# rapidshark-display-shifter-mk-1_1.net
KiCad netlist of a schematic drawn in EAGLE
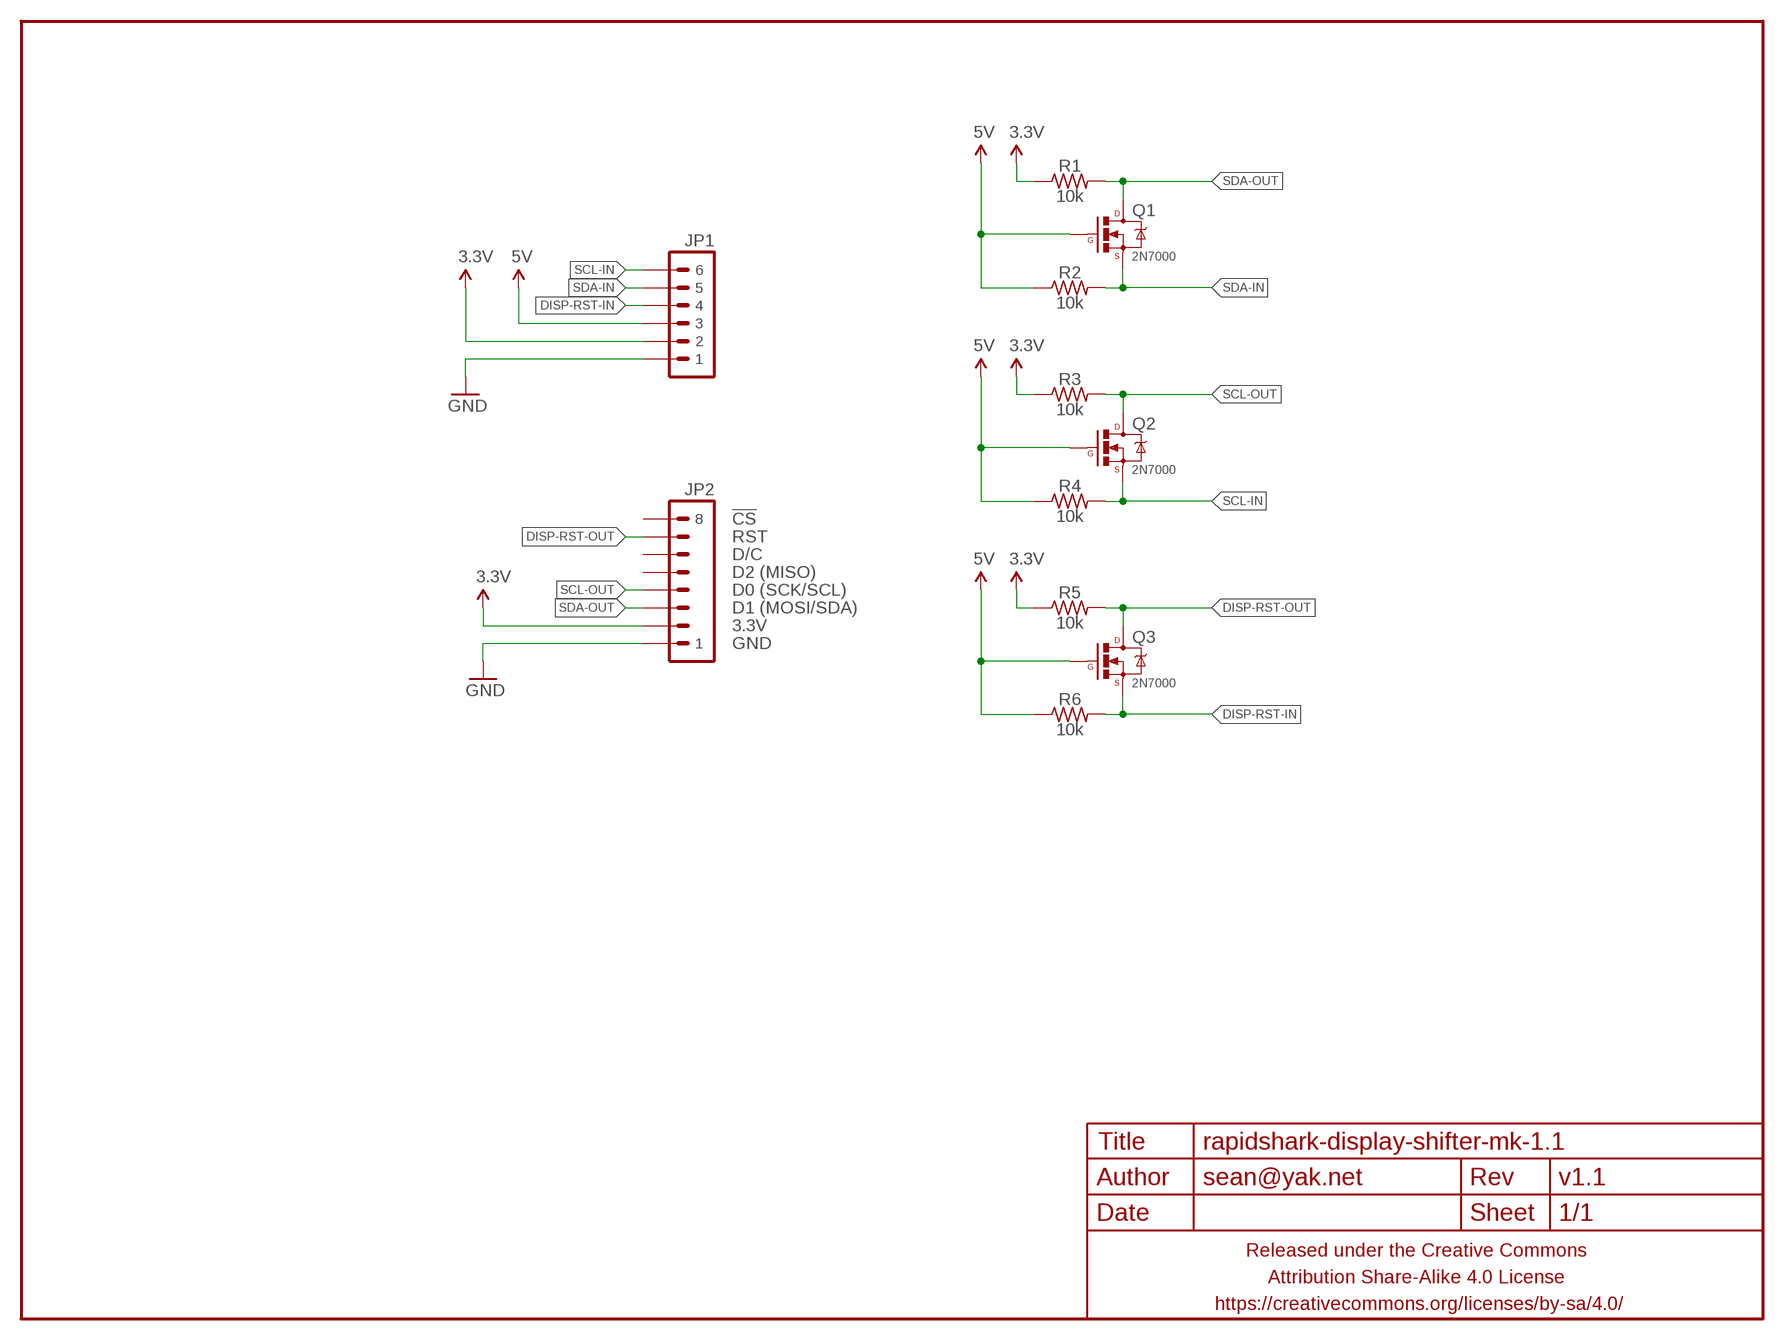
[diagram p0: schematic, sheet 1]

(export (version "E")
  (design (tool "Eeschema 10.0.6"))
  (components
    (comp (ref "FRAME1")
      (value "FRAME-LETTERNO_PACKAGE")
      (footprint "eagle-import:DUMMY")
      (fields (field (name "DESIGNER") "sean@yak.net") (field (name "VERSION") "v1.1"))
      (libsource (lib "eagle-import") (part "FRAME-LETTERNO_PACKAGE"))
    )
    (comp (ref "JP1")
      (value "M06JST-PH-PTH-VERT")
      (footprint "eagle-import:JST-6-PH-VERT-PTH")
      (libsource (lib "eagle-import") (part "M06JST-PH-PTH-VERT"))
    )
    (comp (ref "JP2")
      (value "M081X08")
      (footprint "eagle-import:1X08")
      (libsource (lib "eagle-import") (part "M081X08"))
    )
    (comp (ref "Q1")
      (value "2N7000")
      (footprint "eagle-import:TO-92-AMMO")
      (libsource (lib "eagle-import") (part "MOSFET-NCHANNEL2N7000-AMMO"))
    )
    (comp (ref "Q2")
      (value "2N7000")
      (footprint "eagle-import:TO-92-AMMO")
      (libsource (lib "eagle-import") (part "MOSFET-NCHANNEL2N7000-AMMO"))
    )
    (comp (ref "Q3")
      (value "2N7000")
      (footprint "eagle-import:TO-92-AMMO")
      (libsource (lib "eagle-import") (part "MOSFET-NCHANNEL2N7000-AMMO"))
    )
    (comp (ref "R1")
      (value "10k")
      (footprint "eagle-import:RESISTOR-AXIAL-PTH-5.08MM")
      (libsource (lib "eagle-import") (part "RESISTORPTH-AXIAL-5.08MM"))
    )
    (comp (ref "R2")
      (value "10k")
      (footprint "eagle-import:RESISTOR-AXIAL-PTH-5.08MM")
      (libsource (lib "eagle-import") (part "RESISTORPTH-AXIAL-5.08MM"))
    )
    (comp (ref "R3")
      (value "10k")
      (footprint "eagle-import:RESISTOR-AXIAL-PTH-5.08MM")
      (libsource (lib "eagle-import") (part "RESISTORPTH-AXIAL-5.08MM"))
    )
    (comp (ref "R4")
      (value "10k")
      (footprint "eagle-import:RESISTOR-AXIAL-PTH-5.08MM")
      (libsource (lib "eagle-import") (part "RESISTORPTH-AXIAL-5.08MM"))
    )
    (comp (ref "R5")
      (value "10k")
      (footprint "eagle-import:RESISTOR-AXIAL-PTH-5.08MM")
      (libsource (lib "eagle-import") (part "RESISTORPTH-AXIAL-5.08MM"))
    )
    (comp (ref "R6")
      (value "10k")
      (footprint "eagle-import:RESISTOR-AXIAL-PTH-5.08MM")
      (libsource (lib "eagle-import") (part "RESISTORPTH-AXIAL-5.08MM"))
    )
  )
  (nets
    (net (code "1") (name "3.3V") (class "Default")
      (node (ref "JP1") (pin "2") (pinfunction "2_2") (pintype "passive"))
      (node (ref "JP2") (pin "2") (pinfunction "2_2") (pintype "passive"))
      (node (ref "R1") (pin "P$1") (pinfunction "1_P$1") (pintype "passive"))
      (node (ref "R3") (pin "P$1") (pinfunction "1_P$1") (pintype "passive"))
      (node (ref "R5") (pin "P$1") (pinfunction "1_P$1") (pintype "passive"))
    )
    (net (code "2") (name "5V") (class "Default")
      (node (ref "JP1") (pin "3") (pinfunction "3_3") (pintype "passive"))
      (node (ref "Q1") (pin "2") (pinfunction "G_2") (pintype "passive"))
      (node (ref "Q2") (pin "2") (pinfunction "G_2") (pintype "passive"))
      (node (ref "Q3") (pin "2") (pinfunction "G_2") (pintype "passive"))
      (node (ref "R2") (pin "P$1") (pinfunction "1_P$1") (pintype "passive"))
      (node (ref "R4") (pin "P$1") (pinfunction "1_P$1") (pintype "passive"))
      (node (ref "R6") (pin "P$1") (pinfunction "1_P$1") (pintype "passive"))
    )
    (net (code "3") (name "DISP-RST-IN") (class "Default")
      (node (ref "JP1") (pin "4") (pinfunction "4_4") (pintype "passive"))
      (node (ref "Q3") (pin "1") (pinfunction "S_1") (pintype "passive"))
      (node (ref "R6") (pin "P$2") (pinfunction "2_P$2") (pintype "passive"))
    )
    (net (code "4") (name "DISP-RST-OUT") (class "Default")
      (node (ref "JP2") (pin "7") (pinfunction "7_7") (pintype "passive"))
      (node (ref "Q3") (pin "3") (pinfunction "D_3") (pintype "passive"))
      (node (ref "R5") (pin "P$2") (pinfunction "2_P$2") (pintype "passive"))
    )
    (net (code "5") (name "GND") (class "Default")
      (node (ref "JP1") (pin "1") (pinfunction "1_1") (pintype "passive"))
      (node (ref "JP2") (pin "1") (pinfunction "1_1") (pintype "passive"))
    )
    (net (code "6") (name "SCL-IN") (class "Default")
      (node (ref "JP1") (pin "6") (pinfunction "6_6") (pintype "passive"))
      (node (ref "Q2") (pin "1") (pinfunction "S_1") (pintype "passive"))
      (node (ref "R4") (pin "P$2") (pinfunction "2_P$2") (pintype "passive"))
    )
    (net (code "7") (name "SCL-OUT") (class "Default")
      (node (ref "JP2") (pin "4") (pinfunction "4_4") (pintype "passive"))
      (node (ref "Q2") (pin "3") (pinfunction "D_3") (pintype "passive"))
      (node (ref "R3") (pin "P$2") (pinfunction "2_P$2") (pintype "passive"))
    )
    (net (code "8") (name "SDA-IN") (class "Default")
      (node (ref "JP1") (pin "5") (pinfunction "5_5") (pintype "passive"))
      (node (ref "Q1") (pin "1") (pinfunction "S_1") (pintype "passive"))
      (node (ref "R2") (pin "P$2") (pinfunction "2_P$2") (pintype "passive"))
    )
    (net (code "9") (name "SDA-OUT") (class "Default")
      (node (ref "JP2") (pin "3") (pinfunction "3_3") (pintype "passive"))
      (node (ref "Q1") (pin "3") (pinfunction "D_3") (pintype "passive"))
      (node (ref "R1") (pin "P$2") (pinfunction "2_P$2") (pintype "passive"))
    )
    (net (code "10") (name "unconnected-(JP2-Pad5)") (class "Default")
      (node (ref "JP2") (pin "5") (pinfunction "5_5") (pintype "passive"))
    )
    (net (code "11") (name "unconnected-(JP2-Pad6)") (class "Default")
      (node (ref "JP2") (pin "6") (pinfunction "6_6") (pintype "passive"))
    )
    (net (code "12") (name "unconnected-(JP2-Pad8)") (class "Default")
      (node (ref "JP2") (pin "8") (pinfunction "8_8") (pintype "passive"))
    )
  )
)
